# M706D.net
KiCad netlist of a schematic drawn in EAGLE
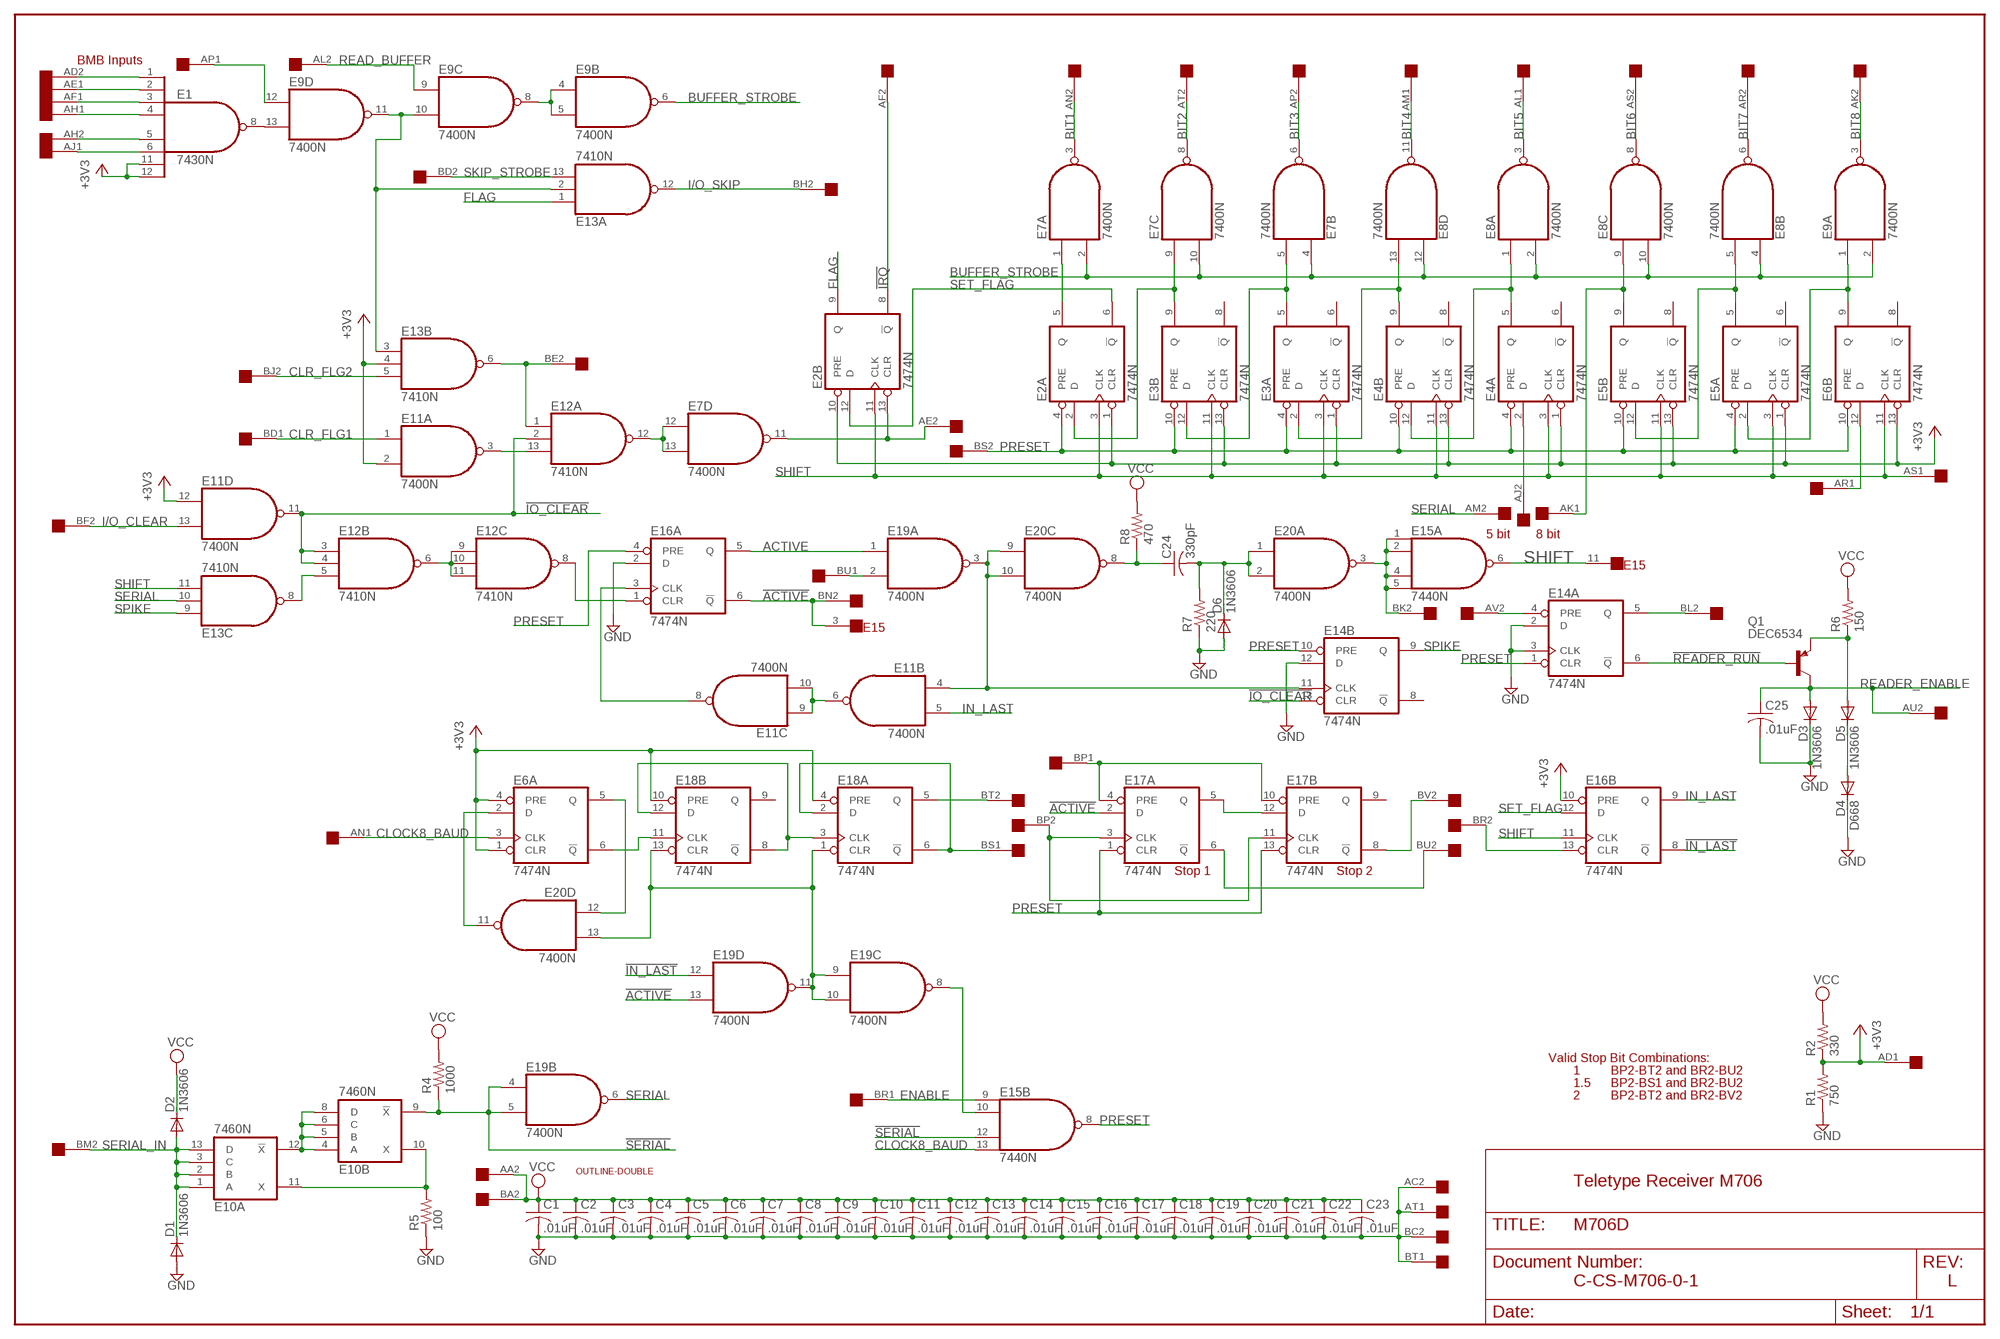
[diagram p0: schematic, sheet 1]

(export (version "E")
  (design (tool "Eeschema 10.0.6"))
  (components
    (comp (ref "C1")
      (value ".01uF")
      (footprint "eagle-import:C075-032X103")
      (libsource (lib "eagle-import") (part "C-US075-032X103"))
    )
    (comp (ref "C2")
      (value ".01uF")
      (footprint "eagle-import:C075-032X103")
      (libsource (lib "eagle-import") (part "C-US075-032X103"))
    )
    (comp (ref "C3")
      (value ".01uF")
      (footprint "eagle-import:C075-032X103")
      (libsource (lib "eagle-import") (part "C-US075-032X103"))
    )
    (comp (ref "C4")
      (value ".01uF")
      (footprint "eagle-import:C075-032X103")
      (libsource (lib "eagle-import") (part "C-US075-032X103"))
    )
    (comp (ref "C5")
      (value ".01uF")
      (footprint "eagle-import:C075-032X103")
      (libsource (lib "eagle-import") (part "C-US075-032X103"))
    )
    (comp (ref "C6")
      (value ".01uF")
      (footprint "eagle-import:C075-032X103")
      (libsource (lib "eagle-import") (part "C-US075-032X103"))
    )
    (comp (ref "C7")
      (value ".01uF")
      (footprint "eagle-import:C075-032X103")
      (libsource (lib "eagle-import") (part "C-US075-032X103"))
    )
    (comp (ref "C8")
      (value ".01uF")
      (footprint "eagle-import:C075-032X103")
      (libsource (lib "eagle-import") (part "C-US075-032X103"))
    )
    (comp (ref "C9")
      (value ".01uF")
      (footprint "eagle-import:C075-032X103")
      (libsource (lib "eagle-import") (part "C-US075-032X103"))
    )
    (comp (ref "C10")
      (value ".01uF")
      (footprint "eagle-import:C075-032X103")
      (libsource (lib "eagle-import") (part "C-US075-032X103"))
    )
    (comp (ref "C11")
      (value ".01uF")
      (footprint "eagle-import:C075-032X103")
      (libsource (lib "eagle-import") (part "C-US075-032X103"))
    )
    (comp (ref "C12")
      (value ".01uF")
      (footprint "eagle-import:C075-032X103")
      (libsource (lib "eagle-import") (part "C-US075-032X103"))
    )
    (comp (ref "C13")
      (value ".01uF")
      (footprint "eagle-import:C075-032X103")
      (libsource (lib "eagle-import") (part "C-US075-032X103"))
    )
    (comp (ref "C14")
      (value ".01uF")
      (footprint "eagle-import:C075-032X103")
      (libsource (lib "eagle-import") (part "C-US075-032X103"))
    )
    (comp (ref "C15")
      (value ".01uF")
      (footprint "eagle-import:C075-032X103")
      (libsource (lib "eagle-import") (part "C-US075-032X103"))
    )
    (comp (ref "C16")
      (value ".01uF")
      (footprint "eagle-import:C075-032X103")
      (libsource (lib "eagle-import") (part "C-US075-032X103"))
    )
    (comp (ref "C17")
      (value ".01uF")
      (footprint "eagle-import:C075-032X103")
      (libsource (lib "eagle-import") (part "C-US075-032X103"))
    )
    (comp (ref "C18")
      (value ".01uF")
      (footprint "eagle-import:C075-032X103")
      (libsource (lib "eagle-import") (part "C-US075-032X103"))
    )
    (comp (ref "C19")
      (value ".01uF")
      (footprint "eagle-import:C075-032X103")
      (libsource (lib "eagle-import") (part "C-US075-032X103"))
    )
    (comp (ref "C20")
      (value ".01uF")
      (footprint "eagle-import:C075-032X103")
      (libsource (lib "eagle-import") (part "C-US075-032X103"))
    )
    (comp (ref "C21")
      (value ".01uF")
      (footprint "eagle-import:C075-032X103")
      (libsource (lib "eagle-import") (part "C-US075-032X103"))
    )
    (comp (ref "C22")
      (value ".01uF")
      (footprint "eagle-import:C075-032X103")
      (libsource (lib "eagle-import") (part "C-US075-032X103"))
    )
    (comp (ref "C23")
      (value ".01uF")
      (footprint "eagle-import:C075-032X103")
      (libsource (lib "eagle-import") (part "C-US075-032X103"))
    )
    (comp (ref "C24")
      (value "330pF")
      (footprint "eagle-import:C075-032X103")
      (libsource (lib "eagle-import") (part "C-US075-032X103"))
    )
    (comp (ref "C25")
      (value ".01uF")
      (footprint "eagle-import:C075-032X103")
      (libsource (lib "eagle-import") (part "C-US075-032X103"))
    )
    (comp (ref "D1")
      (value "1N3606")
      (footprint "eagle-import:SOD61B")
      (libsource (lib "eagle-import") (part "DIODE-SOD61B"))
    )
    (comp (ref "D2")
      (value "1N3606")
      (footprint "eagle-import:SOD61B")
      (libsource (lib "eagle-import") (part "DIODE-SOD61B"))
    )
    (comp (ref "D3")
      (value "1N3606")
      (footprint "eagle-import:DO35-10")
      (libsource (lib "eagle-import") (part "1N4148DO35-10"))
    )
    (comp (ref "D4")
      (value "D668")
      (footprint "eagle-import:DO35-10")
      (libsource (lib "eagle-import") (part "1N4148DO35-10"))
    )
    (comp (ref "D5")
      (value "1N3606")
      (footprint "eagle-import:DO35-10")
      (libsource (lib "eagle-import") (part "1N4148DO35-10"))
    )
    (comp (ref "D6")
      (value "1N3606")
      (footprint "eagle-import:SOD61B")
      (libsource (lib "eagle-import") (part "DIODE-SOD61B"))
    )
    (comp (ref "E1")
      (value "7430N")
      (footprint "eagle-import:DIL14")
      (libsource (lib "eagle-import") (part "7430N"))
    )
    (comp (ref "E2")
      (value "7474N")
      (footprint "eagle-import:DIL14")
      (libsource (lib "eagle-import") (part "7474NS"))
    )
    (comp (ref "E3")
      (value "7474N")
      (footprint "eagle-import:DIL14")
      (libsource (lib "eagle-import") (part "7474NS"))
    )
    (comp (ref "E4")
      (value "7474N")
      (footprint "eagle-import:DIL14")
      (libsource (lib "eagle-import") (part "7474NS"))
    )
    (comp (ref "E5")
      (value "7474N")
      (footprint "eagle-import:DIL14")
      (libsource (lib "eagle-import") (part "7474NS"))
    )
    (comp (ref "E6")
      (value "7474N")
      (footprint "eagle-import:DIL14")
      (libsource (lib "eagle-import") (part "7474NS"))
    )
    (comp (ref "E7")
      (value "7400N")
      (footprint "eagle-import:DIL14")
      (libsource (lib "eagle-import") (part "7400N"))
    )
    (comp (ref "E8")
      (value "7400N")
      (footprint "eagle-import:DIL14")
      (libsource (lib "eagle-import") (part "7400N"))
    )
    (comp (ref "E9")
      (value "7400N")
      (footprint "eagle-import:DIL14")
      (libsource (lib "eagle-import") (part "7400N"))
    )
    (comp (ref "E10")
      (value "7460N")
      (footprint "eagle-import:DIL14")
      (libsource (lib "eagle-import") (part "7460N"))
    )
    (comp (ref "E11")
      (value "7400N")
      (footprint "eagle-import:DIL14")
      (libsource (lib "eagle-import") (part "7400N"))
    )
    (comp (ref "E12")
      (value "7410N")
      (footprint "eagle-import:DIL14")
      (libsource (lib "eagle-import") (part "7410N"))
    )
    (comp (ref "E13")
      (value "7410N")
      (footprint "eagle-import:DIL14")
      (libsource (lib "eagle-import") (part "7410N"))
    )
    (comp (ref "E14")
      (value "7474N")
      (footprint "eagle-import:DIL14")
      (libsource (lib "eagle-import") (part "7474NS"))
    )
    (comp (ref "E15")
      (value "7440N")
      (footprint "eagle-import:DIL14")
      (libsource (lib "eagle-import") (part "7440NS"))
    )
    (comp (ref "E16")
      (value "7474N")
      (footprint "eagle-import:DIL14")
      (libsource (lib "eagle-import") (part "7474NS"))
    )
    (comp (ref "E17")
      (value "7474N")
      (footprint "eagle-import:DIL14")
      (libsource (lib "eagle-import") (part "7474NS"))
    )
    (comp (ref "E18")
      (value "7474N")
      (footprint "eagle-import:DIL14")
      (libsource (lib "eagle-import") (part "7474NS"))
    )
    (comp (ref "E19")
      (value "7400N")
      (footprint "eagle-import:DIL14")
      (libsource (lib "eagle-import") (part "7400N"))
    )
    (comp (ref "E20")
      (value "7400N")
      (footprint "eagle-import:DIL14")
      (libsource (lib "eagle-import") (part "7400N"))
    )
    (comp (ref "Q1")
      (value "DEC6534")
      (footprint "eagle-import:TO92-EBC")
      (libsource (lib "eagle-import") (part "-PNP-TO92-EBCBC327-16"))
    )
    (comp (ref "R1")
      (value "750")
      (footprint "eagle-import:0207_10")
      (libsource (lib "eagle-import") (part "R-US_0207/10"))
    )
    (comp (ref "R2")
      (value "330")
      (footprint "eagle-import:0207_10")
      (libsource (lib "eagle-import") (part "R-US_0207/10"))
    )
    (comp (ref "R4")
      (value "1000")
      (footprint "eagle-import:0207_15")
      (libsource (lib "eagle-import") (part "R-US_0207/15"))
    )
    (comp (ref "R5")
      (value "100")
      (footprint "eagle-import:0207_15")
      (libsource (lib "eagle-import") (part "R-US_0207/15"))
    )
    (comp (ref "R6")
      (value "150")
      (footprint "eagle-import:0207_10")
      (libsource (lib "eagle-import") (part "R-US_0207/10"))
    )
    (comp (ref "R7")
      (value "220")
      (footprint "eagle-import:0207_15")
      (libsource (lib "eagle-import") (part "R-US_0207/15"))
    )
    (comp (ref "R8")
      (value "470")
      (footprint "eagle-import:0207_15")
      (libsource (lib "eagle-import") (part "R-US_0207/15"))
    )
    (comp (ref "U$1")
      (value "OUTLINE-DOUBLE")
      (footprint "eagle-import:DOUBLE")
      (libsource (lib "eagle-import") (part "OUTLINE-DOUBLE"))
    )
    (comp (ref "U$2")
      (value "DOUBLE")
      (footprint "eagle-import:EDGE-CON4")
      (libsource (lib "eagle-import") (part "DOUBLE"))
    )
  )
  (nets
    (net (code "1") (name "+3V3") (class "Default")
      (node (ref "E1") (pin "11") (pinfunction "I6_11") (pintype "input"))
      (node (ref "E1") (pin "12") (pinfunction "I7_12") (pintype "input"))
      (node (ref "E11") (pin "12") (pinfunction "I0_12") (pintype "input"))
      (node (ref "E11") (pin "2") (pinfunction "I1_2") (pintype "input"))
      (node (ref "E13") (pin "4") (pinfunction "I1_4") (pintype "input"))
      (node (ref "E16") (pin "10") (pinfunction "PRE_10") (pintype "input"))
      (node (ref "E18") (pin "10") (pinfunction "PRE_10") (pintype "input"))
      (node (ref "E18") (pin "4") (pinfunction "PRE_4") (pintype "input"))
      (node (ref "E2") (pin "1") (pinfunction "CLR_1") (pintype "input"))
      (node (ref "E2") (pin "10") (pinfunction "PRE_10") (pintype "input"))
      (node (ref "E3") (pin "1") (pinfunction "CLR_1") (pintype "input"))
      (node (ref "E3") (pin "13") (pinfunction "CLR_13") (pintype "input"))
      (node (ref "E4") (pin "1") (pinfunction "CLR_1") (pintype "input"))
      (node (ref "E4") (pin "13") (pinfunction "CLR_13") (pintype "input"))
      (node (ref "E5") (pin "1") (pinfunction "CLR_1") (pintype "input"))
      (node (ref "E5") (pin "13") (pinfunction "CLR_13") (pintype "input"))
      (node (ref "E6") (pin "1") (pinfunction "CLR_1") (pintype "input"))
      (node (ref "E6") (pin "13") (pinfunction "CLR_13") (pintype "input"))
      (node (ref "E6") (pin "4") (pinfunction "PRE_4") (pintype "input"))
      (node (ref "R1") (pin "2") (pinfunction "2_2") (pintype "passive"))
      (node (ref "R2") (pin "1") (pinfunction "1_1") (pintype "passive"))
      (node (ref "U$2") (pin "AD1") (pinfunction "1_AD1") (pintype "bidirectional"))
    )
    (net (code "2") (name "/ACTIVE") (class "Default")
      (node (ref "E16") (pin "5") (pinfunction "Q_5") (pintype "output"))
      (node (ref "E19") (pin "1") (pinfunction "I0_1") (pintype "input"))
    )
    (net (code "3") (name "/BIT1") (class "Default")
      (node (ref "E7") (pin "3") (pinfunction "O_3") (pintype "output"))
      (node (ref "U$2") (pin "AN2") (pinfunction "1_AN2") (pintype "bidirectional"))
    )
    (net (code "4") (name "/BIT2") (class "Default")
      (node (ref "E7") (pin "8") (pinfunction "O_8") (pintype "output"))
      (node (ref "U$2") (pin "AT2") (pinfunction "1_AT2") (pintype "bidirectional"))
    )
    (net (code "5") (name "/BIT3") (class "Default")
      (node (ref "E7") (pin "6") (pinfunction "O_6") (pintype "output"))
      (node (ref "U$2") (pin "AP2") (pinfunction "1_AP2") (pintype "bidirectional"))
    )
    (net (code "6") (name "/BIT4") (class "Default")
      (node (ref "E8") (pin "11") (pinfunction "O_11") (pintype "output"))
      (node (ref "U$2") (pin "AM1") (pinfunction "1_AM1") (pintype "bidirectional"))
    )
    (net (code "7") (name "/BIT5") (class "Default")
      (node (ref "E8") (pin "3") (pinfunction "O_3") (pintype "output"))
      (node (ref "U$2") (pin "AL1") (pinfunction "1_AL1") (pintype "bidirectional"))
    )
    (net (code "8") (name "/BIT6") (class "Default")
      (node (ref "E8") (pin "8") (pinfunction "O_8") (pintype "output"))
      (node (ref "U$2") (pin "AS2") (pinfunction "1_AS2") (pintype "bidirectional"))
    )
    (net (code "9") (name "/BIT7") (class "Default")
      (node (ref "E8") (pin "6") (pinfunction "O_6") (pintype "output"))
      (node (ref "U$2") (pin "AR2") (pinfunction "1_AR2") (pintype "bidirectional"))
    )
    (net (code "10") (name "/BIT8") (class "Default")
      (node (ref "E9") (pin "3") (pinfunction "O_3") (pintype "output"))
      (node (ref "U$2") (pin "AK2") (pinfunction "1_AK2") (pintype "bidirectional"))
    )
    (net (code "11") (name "/BUFFER_STROBE") (class "Default")
      (node (ref "E7") (pin "10") (pinfunction "I1_10") (pintype "input"))
      (node (ref "E7") (pin "2") (pinfunction "I1_2") (pintype "input"))
      (node (ref "E7") (pin "4") (pinfunction "I0_4") (pintype "input"))
      (node (ref "E8") (pin "10") (pinfunction "I1_10") (pintype "input"))
      (node (ref "E8") (pin "12") (pinfunction "I0_12") (pintype "input"))
      (node (ref "E8") (pin "2") (pinfunction "I1_2") (pintype "input"))
      (node (ref "E8") (pin "4") (pinfunction "I0_4") (pintype "input"))
      (node (ref "E9") (pin "2") (pinfunction "I1_2") (pintype "input"))
      (node (ref "E9") (pin "6") (pinfunction "O_6") (pintype "output"))
    )
    (net (code "12") (name "/CLOCK8_BAUD") (class "Default")
      (node (ref "E15") (pin "13") (pinfunction "I3_13") (pintype "input"))
      (node (ref "E6") (pin "3") (pinfunction "CLK_3") (pintype "input"))
      (node (ref "U$2") (pin "AN1") (pinfunction "1_AN1") (pintype "bidirectional"))
    )
    (net (code "13") (name "/CLR_FLG1") (class "Default")
      (node (ref "E11") (pin "1") (pinfunction "I0_1") (pintype "input"))
      (node (ref "U$2") (pin "BD1") (pinfunction "1_BD1") (pintype "bidirectional"))
    )
    (net (code "14") (name "/CLR_FLG2") (class "Default")
      (node (ref "E13") (pin "5") (pinfunction "I2_5") (pintype "input"))
      (node (ref "U$2") (pin "BJ2") (pinfunction "1_BJ2") (pintype "bidirectional"))
    )
    (net (code "15") (name "/ENABLE") (class "Default")
      (node (ref "E15") (pin "9") (pinfunction "I0_9") (pintype "input"))
      (node (ref "U$2") (pin "BR1") (pinfunction "1_BR1") (pintype "bidirectional"))
    )
    (net (code "16") (name "/FLAG") (class "Default")
      (node (ref "E13") (pin "1") (pinfunction "I0_1") (pintype "input"))
      (node (ref "E2") (pin "9") (pinfunction "Q_9") (pintype "output"))
    )
    (net (code "17") (name "/IN_LAST") (class "Default")
      (node (ref "E11") (pin "5") (pinfunction "I1_5") (pintype "input"))
      (node (ref "E16") (pin "9") (pinfunction "Q_9") (pintype "output"))
    )
    (net (code "18") (name "/I{slash}O_CLEAR") (class "Default")
      (node (ref "E11") (pin "13") (pinfunction "I1_13") (pintype "input"))
      (node (ref "U$2") (pin "BF2") (pinfunction "1_BF2") (pintype "bidirectional"))
    )
    (net (code "19") (name "/I{slash}O_SKIP") (class "Default")
      (node (ref "E13") (pin "12") (pinfunction "O_12") (pintype "output"))
      (node (ref "U$2") (pin "BH2") (pinfunction "1_BH2") (pintype "bidirectional"))
    )
    (net (code "20") (name "/PRESET") (class "Default")
      (node (ref "E14") (pin "1") (pinfunction "CLR_1") (pintype "input"))
      (node (ref "E14") (pin "10") (pinfunction "PRE_10") (pintype "input"))
      (node (ref "E15") (pin "8") (pinfunction "O_8") (pintype "output"))
      (node (ref "E16") (pin "4") (pinfunction "PRE_4") (pintype "input"))
      (node (ref "E17") (pin "1") (pinfunction "CLR_1") (pintype "input"))
      (node (ref "E17") (pin "13") (pinfunction "CLR_13") (pintype "input"))
      (node (ref "E2") (pin "4") (pinfunction "PRE_4") (pintype "input"))
      (node (ref "E3") (pin "10") (pinfunction "PRE_10") (pintype "input"))
      (node (ref "E3") (pin "4") (pinfunction "PRE_4") (pintype "input"))
      (node (ref "E4") (pin "10") (pinfunction "PRE_10") (pintype "input"))
      (node (ref "E4") (pin "4") (pinfunction "PRE_4") (pintype "input"))
      (node (ref "E5") (pin "10") (pinfunction "PRE_10") (pintype "input"))
      (node (ref "E5") (pin "4") (pinfunction "PRE_4") (pintype "input"))
      (node (ref "E6") (pin "10") (pinfunction "PRE_10") (pintype "input"))
      (node (ref "U$2") (pin "BS2") (pinfunction "1_BS2") (pintype "bidirectional"))
    )
    (net (code "21") (name "/READER_ENABLE") (class "Default")
      (node (ref "C25") (pin "1") (pinfunction "1_1") (pintype "passive"))
      (node (ref "D3") (pin "A") (pinfunction "A_A") (pintype "passive"))
      (node (ref "Q1") (pin "C") (pinfunction "C_C") (pintype "passive"))
      (node (ref "U$2") (pin "AU2") (pinfunction "1_AU2") (pintype "bidirectional"))
    )
    (net (code "22") (name "/READ_BUFFER") (class "Default")
      (node (ref "E9") (pin "9") (pinfunction "I0_9") (pintype "input"))
      (node (ref "U$2") (pin "AL2") (pinfunction "1_AL2") (pintype "bidirectional"))
    )
    (net (code "23") (name "/SERIAL") (class "Default")
      (node (ref "E13") (pin "10") (pinfunction "I1_10") (pintype "input"))
      (node (ref "E19") (pin "6") (pinfunction "O_6") (pintype "output"))
      (node (ref "U$2") (pin "AM2") (pinfunction "1_AM2") (pintype "bidirectional"))
    )
    (net (code "24") (name "/SERIAL_IN") (class "Default")
      (node (ref "D1") (pin "C") (pinfunction "C_C") (pintype "passive"))
      (node (ref "D2") (pin "A") (pinfunction "A_A") (pintype "passive"))
      (node (ref "E10") (pin "1") (pinfunction "A_1") (pintype "input"))
      (node (ref "E10") (pin "13") (pinfunction "D_13") (pintype "input"))
      (node (ref "E10") (pin "2") (pinfunction "B_2") (pintype "input"))
      (node (ref "E10") (pin "3") (pinfunction "C_3") (pintype "input"))
      (node (ref "U$2") (pin "BM2") (pinfunction "1_BM2") (pintype "bidirectional"))
    )
    (net (code "25") (name "/SET_FLAG") (class "Default")
      (node (ref "E16") (pin "12") (pinfunction "D_12") (pintype "input"))
      (node (ref "E2") (pin "12") (pinfunction "D_12") (pintype "input"))
      (node (ref "E2") (pin "6") (pinfunction "~{Q}_6") (pintype "output"))
    )
    (net (code "26") (name "/SHIFT") (class "Default")
      (node (ref "E13") (pin "11") (pinfunction "I2_11") (pintype "input"))
      (node (ref "E15") (pin "11") (pinfunction "NC_11") (pintype "passive"))
      (node (ref "E15") (pin "6") (pinfunction "O_6") (pintype "output"))
      (node (ref "E16") (pin "11") (pinfunction "CLK_11") (pintype "input"))
      (node (ref "E2") (pin "11") (pinfunction "CLK_11") (pintype "input"))
      (node (ref "E2") (pin "3") (pinfunction "CLK_3") (pintype "input"))
      (node (ref "E3") (pin "11") (pinfunction "CLK_11") (pintype "input"))
      (node (ref "E3") (pin "3") (pinfunction "CLK_3") (pintype "input"))
      (node (ref "E4") (pin "11") (pinfunction "CLK_11") (pintype "input"))
      (node (ref "E4") (pin "3") (pinfunction "CLK_3") (pintype "input"))
      (node (ref "E5") (pin "11") (pinfunction "CLK_11") (pintype "input"))
      (node (ref "E5") (pin "3") (pinfunction "CLK_3") (pintype "input"))
      (node (ref "E6") (pin "11") (pinfunction "CLK_11") (pintype "input"))
      (node (ref "U$2") (pin "AS1") (pinfunction "1_AS1") (pintype "bidirectional"))
    )
    (net (code "27") (name "/SKIP_STROBE") (class "Default")
      (node (ref "E13") (pin "13") (pinfunction "I2_13") (pintype "input"))
      (node (ref "U$2") (pin "BD2") (pinfunction "1_BD2") (pintype "bidirectional"))
    )
    (net (code "28") (name "/SPIKE") (class "Default")
      (node (ref "E13") (pin "9") (pinfunction "I0_9") (pintype "input"))
      (node (ref "E14") (pin "9") (pinfunction "Q_9") (pintype "output"))
    )
    (net (code "29") (name "/~{ACTIVE}") (class "Default")
      (node (ref "E15") (pin "3") (pinfunction "NC_3") (pintype "passive"))
      (node (ref "E16") (pin "6") (pinfunction "~{Q}_6") (pintype "output"))
      (node (ref "E17") (pin "2") (pinfunction "D_2") (pintype "input"))
      (node (ref "E19") (pin "13") (pinfunction "I1_13") (pintype "input"))
      (node (ref "U$2") (pin "BN2") (pinfunction "1_BN2") (pintype "bidirectional"))
    )
    (net (code "30") (name "/~{IN_LAST}") (class "Default")
      (node (ref "E16") (pin "8") (pinfunction "~{Q}_8") (pintype "output"))
      (node (ref "E19") (pin "12") (pinfunction "I0_12") (pintype "input"))
    )
    (net (code "31") (name "/~{IO_CLEAR}") (class "Default")
      (node (ref "E11") (pin "11") (pinfunction "O_11") (pintype "output"))
      (node (ref "E12") (pin "2") (pinfunction "I1_2") (pintype "input"))
      (node (ref "E12") (pin "3") (pinfunction "I0_3") (pintype "input"))
      (node (ref "E12") (pin "4") (pinfunction "I1_4") (pintype "input"))
      (node (ref "E14") (pin "13") (pinfunction "CLR_13") (pintype "input"))
    )
    (net (code "32") (name "/~{IRQ}") (class "Default")
      (node (ref "E2") (pin "8") (pinfunction "~{Q}_8") (pintype "output"))
      (node (ref "U$2") (pin "AF2") (pinfunction "1_AF2") (pintype "bidirectional"))
    )
    (net (code "33") (name "/~{READER_RUN}") (class "Default")
      (node (ref "E14") (pin "6") (pinfunction "~{Q}_6") (pintype "output"))
      (node (ref "Q1") (pin "B") (pinfunction "B_B") (pintype "passive"))
    )
    (net (code "34") (name "/~{SERIAL}") (class "Default")
      (node (ref "E10") (pin "9") (pinfunction "~{X}_9") (pintype "output"))
      (node (ref "E15") (pin "12") (pinfunction "I2_12") (pintype "input"))
      (node (ref "E19") (pin "4") (pinfunction "I0_4") (pintype "input"))
      (node (ref "E19") (pin "5") (pinfunction "I1_5") (pintype "input"))
      (node (ref "R4") (pin "1") (pinfunction "1_1") (pintype "passive"))
    )
    (net (code "35") (name "GND") (class "Default")
      (node (ref "C1") (pin "2") (pinfunction "2_2") (pintype "passive"))
      (node (ref "C10") (pin "2") (pinfunction "2_2") (pintype "passive"))
      (node (ref "C11") (pin "2") (pinfunction "2_2") (pintype "passive"))
      (node (ref "C12") (pin "2") (pinfunction "2_2") (pintype "passive"))
      (node (ref "C13") (pin "2") (pinfunction "2_2") (pintype "passive"))
      (node (ref "C14") (pin "2") (pinfunction "2_2") (pintype "passive"))
      (node (ref "C15") (pin "2") (pinfunction "2_2") (pintype "passive"))
      (node (ref "C16") (pin "2") (pinfunction "2_2") (pintype "passive"))
      (node (ref "C17") (pin "2") (pinfunction "2_2") (pintype "passive"))
      (node (ref "C18") (pin "2") (pinfunction "2_2") (pintype "passive"))
      (node (ref "C19") (pin "2") (pinfunction "2_2") (pintype "passive"))
      (node (ref "C2") (pin "2") (pinfunction "2_2") (pintype "passive"))
      (node (ref "C20") (pin "2") (pinfunction "2_2") (pintype "passive"))
      (node (ref "C21") (pin "2") (pinfunction "2_2") (pintype "passive"))
      (node (ref "C22") (pin "2") (pinfunction "2_2") (pintype "passive"))
      (node (ref "C23") (pin "2") (pinfunction "2_2") (pintype "passive"))
      (node (ref "C25") (pin "2") (pinfunction "2_2") (pintype "passive"))
      (node (ref "C3") (pin "2") (pinfunction "2_2") (pintype "passive"))
      (node (ref "C4") (pin "2") (pinfunction "2_2") (pintype "passive"))
      (node (ref "C5") (pin "2") (pinfunction "2_2") (pintype "passive"))
      (node (ref "C6") (pin "2") (pinfunction "2_2") (pintype "passive"))
      (node (ref "C7") (pin "2") (pinfunction "2_2") (pintype "passive"))
      (node (ref "C8") (pin "2") (pinfunction "2_2") (pintype "passive"))
      (node (ref "C9") (pin "2") (pinfunction "2_2") (pintype "passive"))
      (node (ref "D1") (pin "A") (pinfunction "A_A") (pintype "passive"))
      (node (ref "D3") (pin "C") (pinfunction "C_C") (pintype "passive"))
      (node (ref "D4") (pin "C") (pinfunction "C_C") (pintype "passive"))
      (node (ref "D6") (pin "A") (pinfunction "A_A") (pintype "passive"))
      (node (ref "E14") (pin "12") (pinfunction "D_12") (pintype "input"))
      (node (ref "E14") (pin "2") (pinfunction "D_2") (pintype "input"))
      (node (ref "E14") (pin "3") (pinfunction "CLK_3") (pintype "input"))
      (node (ref "E16") (pin "2") (pinfunction "D_2") (pintype "input"))
      (node (ref "R1") (pin "1") (pinfunction "1_1") (pintype "passive"))
      (node (ref "R5") (pin "1") (pinfunction "1_1") (pintype "passive"))
      (node (ref "R7") (pin "1") (pinfunction "1_1") (pintype "passive"))
      (node (ref "U$2") (pin "AC2") (pinfunction "1_AC2") (pintype "bidirectional"))
      (node (ref "U$2") (pin "AT1") (pinfunction "1_AT1") (pintype "bidirectional"))
      (node (ref "U$2") (pin "BC2") (pinfunction "1_BC2") (pintype "bidirectional"))
      (node (ref "U$2") (pin "BT1") (pinfunction "1_BT1") (pintype "bidirectional"))
    )
    (net (code "36") (name "Net-(D4-PadA)") (class "Default")
      (node (ref "D4") (pin "A") (pinfunction "A_A") (pintype "passive"))
      (node (ref "D5") (pin "C") (pinfunction "C_C") (pintype "passive"))
    )
    (net (code "37") (name "Net-(D5-PadA)") (class "Default")
      (node (ref "D5") (pin "A") (pinfunction "A_A") (pintype "passive"))
      (node (ref "Q1") (pin "E") (pinfunction "E_E") (pintype "passive"))
      (node (ref "R6") (pin "1") (pinfunction "1_1") (pintype "passive"))
    )
    (net (code "38") (name "Net-(E1A-I0)") (class "Default")
      (node (ref "E1") (pin "1") (pinfunction "I0_1") (pintype "input"))
      (node (ref "U$2") (pin "AD2") (pinfunction "1_AD2") (pintype "bidirectional"))
    )
    (net (code "39") (name "Net-(E1A-I1)") (class "Default")
      (node (ref "E1") (pin "2") (pinfunction "I1_2") (pintype "input"))
      (node (ref "U$2") (pin "AE1") (pinfunction "1_AE1") (pintype "bidirectional"))
    )
    (net (code "40") (name "Net-(E1A-I2)") (class "Default")
      (node (ref "E1") (pin "3") (pinfunction "I2_3") (pintype "input"))
      (node (ref "U$2") (pin "AF1") (pinfunction "1_AF1") (pintype "bidirectional"))
    )
    (net (code "41") (name "Net-(E1A-I3)") (class "Default")
      (node (ref "E1") (pin "4") (pinfunction "I3_4") (pintype "input"))
      (node (ref "U$2") (pin "AH1") (pinfunction "1_AH1") (pintype "bidirectional"))
    )
    (net (code "42") (name "Net-(E1A-I4)") (class "Default")
      (node (ref "E1") (pin "5") (pinfunction "I4_5") (pintype "input"))
      (node (ref "U$2") (pin "AH2") (pinfunction "1_AH2") (pintype "bidirectional"))
    )
    (net (code "43") (name "Net-(E1A-I5)") (class "Default")
      (node (ref "E1") (pin "6") (pinfunction "I5_6") (pintype "input"))
      (node (ref "U$2") (pin "AJ1") (pinfunction "1_AJ1") (pintype "bidirectional"))
    )
    (net (code "44") (name "Net-(E1A-O)") (class "Default")
      (node (ref "E1") (pin "8") (pinfunction "O_8") (pintype "output"))
      (node (ref "E9") (pin "13") (pinfunction "I1_13") (pintype "input"))
    )
    (net (code "45") (name "Net-(E2A-D)") (class "Default")
      (node (ref "E2") (pin "2") (pinfunction "D_2") (pintype "input"))
      (node (ref "E3") (pin "9") (pinfunction "Q_9") (pintype "output"))
      (node (ref "E7") (pin "9") (pinfunction "I0_9") (pintype "input"))
    )
    (net (code "46") (name "Net-(E2A-Q)") (class "Default")
      (node (ref "E2") (pin "5") (pinfunction "Q_5") (pintype "output"))
      (node (ref "E7") (pin "1") (pinfunction "I0_1") (pintype "input"))
    )
    (net (code "47") (name "Net-(E2B-CLR)") (class "Default")
      (node (ref "E2") (pin "13") (pinfunction "CLR_13") (pintype "input"))
      (node (ref "E7") (pin "11") (pinfunction "O_11") (pintype "output"))
      (node (ref "U$2") (pin "AE2") (pinfunction "1_AE2") (pintype "bidirectional"))
    )
    (net (code "48") (name "Net-(E3A-D)") (class "Default")
      (node (ref "E3") (pin "2") (pinfunction "D_2") (pintype "input"))
      (node (ref "E4") (pin "9") (pinfunction "Q_9") (pintype "output"))
      (node (ref "E8") (pin "13") (pinfunction "I1_13") (pintype "input"))
    )
    (net (code "49") (name "Net-(E3A-Q)") (class "Default")
      (node (ref "E3") (pin "12") (pinfunction "D_12") (pintype "input"))
      (node (ref "E3") (pin "5") (pinfunction "Q_5") (pintype "output"))
      (node (ref "E7") (pin "5") (pinfunction "I1_5") (pintype "input"))
    )
    (net (code "50") (name "Net-(E4A-D)") (class "Default")
      (node (ref "E4") (pin "2") (pinfunction "D_2") (pintype "input"))
      (node (ref "U$2") (pin "AJ2") (pinfunction "1_AJ2") (pintype "bidirectional"))
    )
    (net (code "51") (name "Net-(E4A-Q)") (class "Default")
      (node (ref "E4") (pin "12") (pinfunction "D_12") (pintype "input"))
      (node (ref "E4") (pin "5") (pinfunction "Q_5") (pintype "output"))
      (node (ref "E8") (pin "1") (pinfunction "I0_1") (pintype "input"))
    )
    (net (code "52") (name "Net-(E5A-D)") (class "Default")
      (node (ref "E5") (pin "2") (pinfunction "D_2") (pintype "input"))
      (node (ref "E6") (pin "9") (pinfunction "Q_9") (pintype "output"))
      (node (ref "E9") (pin "1") (pinfunction "I0_1") (pintype "input"))
    )
    (net (code "53") (name "Net-(E5A-Q)") (class "Default")
      (node (ref "E5") (pin "12") (pinfunction "D_12") (pintype "input"))
      (node (ref "E5") (pin "5") (pinfunction "Q_5") (pintype "output"))
      (node (ref "E8") (pin "5") (pinfunction "I1_5") (pintype "input"))
    )
    (net (code "54") (name "Net-(E5B-Q)") (class "Default")
      (node (ref "E5") (pin "9") (pinfunction "Q_9") (pintype "output"))
      (node (ref "E8") (pin "9") (pinfunction "I0_9") (pintype "input"))
      (node (ref "U$2") (pin "AK1") (pinfunction "1_AK1") (pintype "bidirectional"))
    )
    (net (code "55") (name "Net-(E6B-D)") (class "Default")
      (node (ref "E6") (pin "12") (pinfunction "D_12") (pintype "input"))
      (node (ref "U$2") (pin "AR1") (pinfunction "1_AR1") (pintype "bidirectional"))
    )
    (net (code "56") (name "Net-(E9B-I0)") (class "Default")
      (node (ref "E9") (pin "4") (pinfunction "I0_4") (pintype "input"))
      (node (ref "E9") (pin "5") (pinfunction "I1_5") (pintype "input"))
      (node (ref "E9") (pin "8") (pinfunction "O_8") (pintype "output"))
    )
    (net (code "57") (name "Net-(E9D-I0)") (class "Default")
      (node (ref "E9") (pin "12") (pinfunction "I0_12") (pintype "input"))
      (node (ref "U$2") (pin "AP1") (pinfunction "1_AP1") (pintype "bidirectional"))
    )
    (net (code "58") (name "Net-(E10A-X)") (class "Default")
      (node (ref "E10") (pin "10") (pinfunction "X_10") (pintype "output"))
      (node (ref "E10") (pin "11") (pinfunction "X_11") (pintype "output"))
      (node (ref "R5") (pin "2") (pinfunction "2_2") (pintype "passive"))
    )
    (net (code "59") (name "Net-(E10A-~{X})") (class "Default")
      (node (ref "E10") (pin "12") (pinfunction "~{X}_12") (pintype "output"))
      (node (ref "E10") (pin "4") (pinfunction "A_4") (pintype "input"))
      (node (ref "E10") (pin "5") (pinfunction "B_5") (pintype "input"))
      (node (ref "E10") (pin "6") (pinfunction "C_6") (pintype "input"))
      (node (ref "E10") (pin "8") (pinfunction "D_8") (pintype "input"))
    )
    (net (code "60") (name "Net-(E11A-O)") (class "Default")
      (node (ref "E11") (pin "3") (pinfunction "O_3") (pintype "output"))
      (node (ref "E12") (pin "13") (pinfunction "I2_13") (pintype "input"))
    )
    (net (code "61") (name "Net-(E11B-I0)") (class "Default")
      (node (ref "E11") (pin "4") (pinfunction "I0_4") (pintype "input"))
      (node (ref "E14") (pin "11") (pinfunction "CLK_11") (pintype "input"))
      (node (ref "E19") (pin "3") (pinfunction "O_3") (pintype "output"))
      (node (ref "E20") (pin "10") (pinfunction "I1_10") (pintype "input"))
      (node (ref "E20") (pin "9") (pinfunction "I0_9") (pintype "input"))
    )
    (net (code "62") (name "Net-(E11B-O)") (class "Default")
      (node (ref "E11") (pin "10") (pinfunction "I1_10") (pintype "input"))
      (node (ref "E11") (pin "6") (pinfunction "O_6") (pintype "output"))
      (node (ref "E11") (pin "9") (pinfunction "I0_9") (pintype "input"))
    )
    (net (code "63") (name "Net-(E11C-O)") (class "Default")
      (node (ref "E11") (pin "8") (pinfunction "O_8") (pintype "output"))
      (node (ref "E16") (pin "3") (pinfunction "CLK_3") (pintype "input"))
    )
    (net (code "64") (name "Net-(E12A-I0)") (class "Default")
      (node (ref "E12") (pin "1") (pinfunction "I0_1") (pintype "input"))
      (node (ref "E13") (pin "6") (pinfunction "O_6") (pintype "output"))
      (node (ref "U$2") (pin "BE2") (pinfunction "1_BE2") (pintype "bidirectional"))
    )
    (net (code "65") (name "Net-(E12A-O)") (class "Default")
      (node (ref "E12") (pin "12") (pinfunction "O_12") (pintype "output"))
      (node (ref "E7") (pin "12") (pinfunction "I0_12") (pintype "input"))
      (node (ref "E7") (pin "13") (pinfunction "I1_13") (pintype "input"))
    )
    (net (code "66") (name "Net-(E12B-I2)") (class "Default")
      (node (ref "E12") (pin "5") (pinfunction "I2_5") (pintype "input"))
      (node (ref "E13") (pin "8") (pinfunction "O_8") (pintype "output"))
    )
    (net (code "67") (name "Net-(E12B-O)") (class "Default")
      (node (ref "E12") (pin "10") (pinfunction "I1_10") (pintype "input"))
      (node (ref "E12") (pin "11") (pinfunction "I2_11") (pintype "input"))
      (node (ref "E12") (pin "6") (pinfunction "O_6") (pintype "output"))
      (node (ref "E12") (pin "9") (pinfunction "I0_9") (pintype "input"))
    )
    (net (code "68") (name "Net-(E12C-O)") (class "Default")
      (node (ref "E12") (pin "8") (pinfunction "O_8") (pintype "output"))
      (node (ref "E16") (pin "1") (pinfunction "CLR_1") (pintype "input"))
    )
    (net (code "69") (name "Net-(E13A-I1)") (class "Default")
      (node (ref "E13") (pin "2") (pinfunction "I1_2") (pintype "input"))
      (node (ref "E13") (pin "3") (pinfunction "I0_3") (pintype "input"))
      (node (ref "E9") (pin "10") (pinfunction "I1_10") (pintype "input"))
      (node (ref "E9") (pin "11") (pinfunction "O_11") (pintype "output"))
    )
    (net (code "70") (name "Net-(E14A-PRE)") (class "Default")
      (node (ref "E14") (pin "4") (pinfunction "PRE_4") (pintype "input"))
      (node (ref "U$2") (pin "AV2") (pinfunction "1_AV2") (pintype "bidirectional"))
    )
    (net (code "71") (name "Net-(E14A-Q)") (class "Default")
      (node (ref "E14") (pin "5") (pinfunction "Q_5") (pintype "output"))
      (node (ref "U$2") (pin "BL2") (pinfunction "1_BL2") (pintype "bidirectional"))
    )
    (net (code "72") (name "Net-(E15C-I0)") (class "Default")
      (node (ref "E15") (pin "1") (pinfunction "I0_1") (pintype "input"))
      (node (ref "E15") (pin "2") (pinfunction "I1_2") (pintype "input"))
      (node (ref "E15") (pin "4") (pinfunction "I2_4") (pintype "input"))
      (node (ref "E15") (pin "5") (pinfunction "I3_5") (pintype "input"))
      (node (ref "E20") (pin "3") (pinfunction "O_3") (pintype "output"))
      (node (ref "U$2") (pin "BK2") (pinfunction "1_BK2") (pintype "bidirectional"))
    )
    (net (code "73") (name "Net-(E15D-I1)") (class "Default")
      (node (ref "E15") (pin "10") (pinfunction "I1_10") (pintype "input"))
      (node (ref "E19") (pin "8") (pinfunction "O_8") (pintype "output"))
    )
    (net (code "74") (name "Net-(E16B-CLR)") (class "Default")
      (node (ref "E16") (pin "13") (pinfunction "CLR_13") (pintype "input"))
      (node (ref "U$2") (pin "BR2") (pinfunction "1_BR2") (pintype "bidirectional"))
    )
    (net (code "75") (name "Net-(E17A-CLK)") (class "Default")
      (node (ref "E17") (pin "11") (pinfunction "CLK_11") (pintype "input"))
      (node (ref "E17") (pin "3") (pinfunction "CLK_3") (pintype "input"))
      (node (ref "U$2") (pin "BP2") (pinfunction "1_BP2") (pintype "bidirectional"))
    )
    (net (code "76") (name "Net-(E17A-PRE)") (class "Default")
      (node (ref "E17") (pin "10") (pinfunction "PRE_10") (pintype "input"))
      (node (ref "E17") (pin "4") (pinfunction "PRE_4") (pintype "input"))
      (node (ref "U$2") (pin "BP1") (pinfunction "1_BP1") (pintype "bidirectional"))
    )
    (net (code "77") (name "Net-(E17A-Q)") (class "Default")
      (node (ref "E17") (pin "12") (pinfunction "D_12") (pintype "input"))
      (node (ref "E17") (pin "5") (pinfunction "Q_5") (pintype "output"))
    )
    (net (code "78") (name "Net-(E17A-~{Q})") (class "Default")
      (node (ref "E17") (pin "6") (pinfunction "~{Q}_6") (pintype "output"))
      (node (ref "U$2") (pin "BU2") (pinfunction "1_BU2") (pintype "bidirectional"))
    )
    (net (code "79") (name "Net-(E17B-~{Q})") (class "Default")
      (node (ref "E17") (pin "8") (pinfunction "~{Q}_8") (pintype "output"))
      (node (ref "U$2") (pin "BV2") (pinfunction "1_BV2") (pintype "bidirectional"))
    )
    (net (code "80") (name "Net-(E18A-CLK)") (class "Default")
      (node (ref "E18") (pin "12") (pinfunction "D_12") (pintype "input"))
      (node (ref "E18") (pin "3") (pinfunction "CLK_3") (pintype "input"))
      (node (ref "E18") (pin "8") (pinfunction "~{Q}_8") (pintype "output"))
    )
    (net (code "81") (name "Net-(E18A-CLR)") (class "Default")
      (node (ref "E18") (pin "1") (pinfunction "CLR_1") (pintype "input"))
      (node (ref "E18") (pin "13") (pinfunction "CLR_13") (pintype "input"))
      (node (ref "E19") (pin "10") (pinfunction "I1_10") (pintype "input"))
      (node (ref "E19") (pin "11") (pinfunction "O_11") (pintype "output"))
      (node (ref "E19") (pin "9") (pinfunction "I0_9") (pintype "input"))
      (node (ref "E20") (pin "13") (pinfunction "I1_13") (pintype "input"))
    )
    (net (code "82") (name "Net-(E18A-D)") (class "Default")
      (node (ref "E18") (pin "2") (pinfunction "D_2") (pintype "input"))
      (node (ref "E18") (pin "6") (pinfunction "~{Q}_6") (pintype "output"))
      (node (ref "U$2") (pin "BS1") (pinfunction "1_BS1") (pintype "bidirectional"))
    )
    (net (code "83") (name "Net-(E18A-Q)") (class "Default")
      (node (ref "E18") (pin "5") (pinfunction "Q_5") (pintype "output"))
      (node (ref "U$2") (pin "BT2") (pinfunction "1_BT2") (pintype "bidirectional"))
    )
    (net (code "84") (name "Net-(E18B-CLK)") (class "Default")
      (node (ref "E18") (pin "11") (pinfunction "CLK_11") (pintype "input"))
      (node (ref "E6") (pin "6") (pinfunction "~{Q}_6") (pintype "output"))
    )
    (net (code "85") (name "Net-(E19A-I1)") (class "Default")
      (node (ref "E19") (pin "2") (pinfunction "I1_2") (pintype "input"))
      (node (ref "U$2") (pin "BU1") (pinfunction "1_BU1") (pintype "bidirectional"))
    )
    (net (code "86") (name "Net-(E20A-I0)") (class "Default")
      (node (ref "C24") (pin "2") (pinfunction "2_2") (pintype "passive"))
      (node (ref "D6") (pin "C") (pinfunction "C_C") (pintype "passive"))
      (node (ref "E20") (pin "1") (pinfunction "I0_1") (pintype "input"))
      (node (ref "E20") (pin "2") (pinfunction "I1_2") (pintype "input"))
      (node (ref "R7") (pin "2") (pinfunction "2_2") (pintype "passive"))
    )
    (net (code "87") (name "Net-(E20C-O)") (class "Default")
      (node (ref "C24") (pin "1") (pinfunction "1_1") (pintype "passive"))
      (node (ref "E20") (pin "8") (pinfunction "O_8") (pintype "output"))
      (node (ref "R8") (pin "1") (pinfunction "1_1") (pintype "passive"))
    )
    (net (code "88") (name "Net-(E20D-I0)") (class "Default")
      (node (ref "E20") (pin "12") (pinfunction "I0_12") (pintype "input"))
      (node (ref "E6") (pin "5") (pinfunction "Q_5") (pintype "output"))
    )
    (net (code "89") (name "Net-(E20D-O)") (class "Default")
      (node (ref "E20") (pin "11") (pinfunction "O_11") (pintype "output"))
      (node (ref "E6") (pin "2") (pinfunction "D_2") (pintype "input"))
    )
    (net (code "90") (name "VCC") (class "Default")
      (node (ref "C1") (pin "1") (pinfunction "1_1") (pintype "passive"))
      (node (ref "C10") (pin "1") (pinfunction "1_1") (pintype "passive"))
      (node (ref "C11") (pin "1") (pinfunction "1_1") (pintype "passive"))
      (node (ref "C12") (pin "1") (pinfunction "1_1") (pintype "passive"))
      (node (ref "C13") (pin "1") (pinfunction "1_1") (pintype "passive"))
      (node (ref "C14") (pin "1") (pinfunction "1_1") (pintype "passive"))
      (node (ref "C15") (pin "1") (pinfunction "1_1") (pintype "passive"))
      (node (ref "C16") (pin "1") (pinfunction "1_1") (pintype "passive"))
      (node (ref "C17") (pin "1") (pinfunction "1_1") (pintype "passive"))
      (node (ref "C18") (pin "1") (pinfunction "1_1") (pintype "passive"))
      (node (ref "C19") (pin "1") (pinfunction "1_1") (pintype "passive"))
      (node (ref "C2") (pin "1") (pinfunction "1_1") (pintype "passive"))
      (node (ref "C20") (pin "1") (pinfunction "1_1") (pintype "passive"))
      (node (ref "C21") (pin "1") (pinfunction "1_1") (pintype "passive"))
      (node (ref "C22") (pin "1") (pinfunction "1_1") (pintype "passive"))
      (node (ref "C23") (pin "1") (pinfunction "1_1") (pintype "passive"))
      (node (ref "C3") (pin "1") (pinfunction "1_1") (pintype "passive"))
      (node (ref "C4") (pin "1") (pinfunction "1_1") (pintype "passive"))
      (node (ref "C5") (pin "1") (pinfunction "1_1") (pintype "passive"))
      (node (ref "C6") (pin "1") (pinfunction "1_1") (pintype "passive"))
      (node (ref "C7") (pin "1") (pinfunction "1_1") (pintype "passive"))
      (node (ref "C8") (pin "1") (pinfunction "1_1") (pintype "passive"))
      (node (ref "C9") (pin "1") (pinfunction "1_1") (pintype "passive"))
      (node (ref "D2") (pin "C") (pinfunction "C_C") (pintype "passive"))
      (node (ref "R2") (pin "2") (pinfunction "2_2") (pintype "passive"))
      (node (ref "R4") (pin "2") (pinfunction "2_2") (pintype "passive"))
      (node (ref "R6") (pin "2") (pinfunction "2_2") (pintype "passive"))
      (node (ref "R8") (pin "2") (pinfunction "2_2") (pintype "passive"))
      (node (ref "U$2") (pin "AA2") (pinfunction "1_AA2") (pintype "bidirectional"))
      (node (ref "U$2") (pin "BA2") (pinfunction "1_BA2") (pintype "bidirectional"))
    )
    (net (code "91") (name "unconnected-(E3A-~{Q}-Pad6)") (class "Default")
      (node (ref "E3") (pin "6") (pinfunction "~{Q}_6") (pintype "output"))
    )
    (net (code "92") (name "unconnected-(E3B-~{Q}-Pad8)") (class "Default")
      (node (ref "E3") (pin "8") (pinfunction "~{Q}_8") (pintype "output"))
    )
    (net (code "93") (name "unconnected-(E4A-~{Q}-Pad6)") (class "Default")
      (node (ref "E4") (pin "6") (pinfunction "~{Q}_6") (pintype "output"))
    )
    (net (code "94") (name "unconnected-(E4B-~{Q}-Pad8)") (class "Default")
      (node (ref "E4") (pin "8") (pinfunction "~{Q}_8") (pintype "output"))
    )
    (net (code "95") (name "unconnected-(E5A-~{Q}-Pad6)") (class "Default")
      (node (ref "E5") (pin "6") (pinfunction "~{Q}_6") (pintype "output"))
    )
    (net (code "96") (name "unconnected-(E5B-~{Q}-Pad8)") (class "Default")
      (node (ref "E5") (pin "8") (pinfunction "~{Q}_8") (pintype "output"))
    )
    (net (code "97") (name "unconnected-(E6B-~{Q}-Pad8)") (class "Default")
      (node (ref "E6") (pin "8") (pinfunction "~{Q}_8") (pintype "output"))
    )
    (net (code "98") (name "unconnected-(E14B-~{Q}-Pad8)") (class "Default")
      (node (ref "E14") (pin "8") (pinfunction "~{Q}_8") (pintype "output"))
    )
    (net (code "99") (name "unconnected-(E17B-Q-Pad9)") (class "Default")
      (node (ref "E17") (pin "9") (pinfunction "Q_9") (pintype "output"))
    )
    (net (code "100") (name "unconnected-(E18B-Q-Pad9)") (class "Default")
      (node (ref "E18") (pin "9") (pinfunction "Q_9") (pintype "output"))
    )
  )
)
